# motor_driver.net
KiCad netlist of a schematic drawn in EAGLE
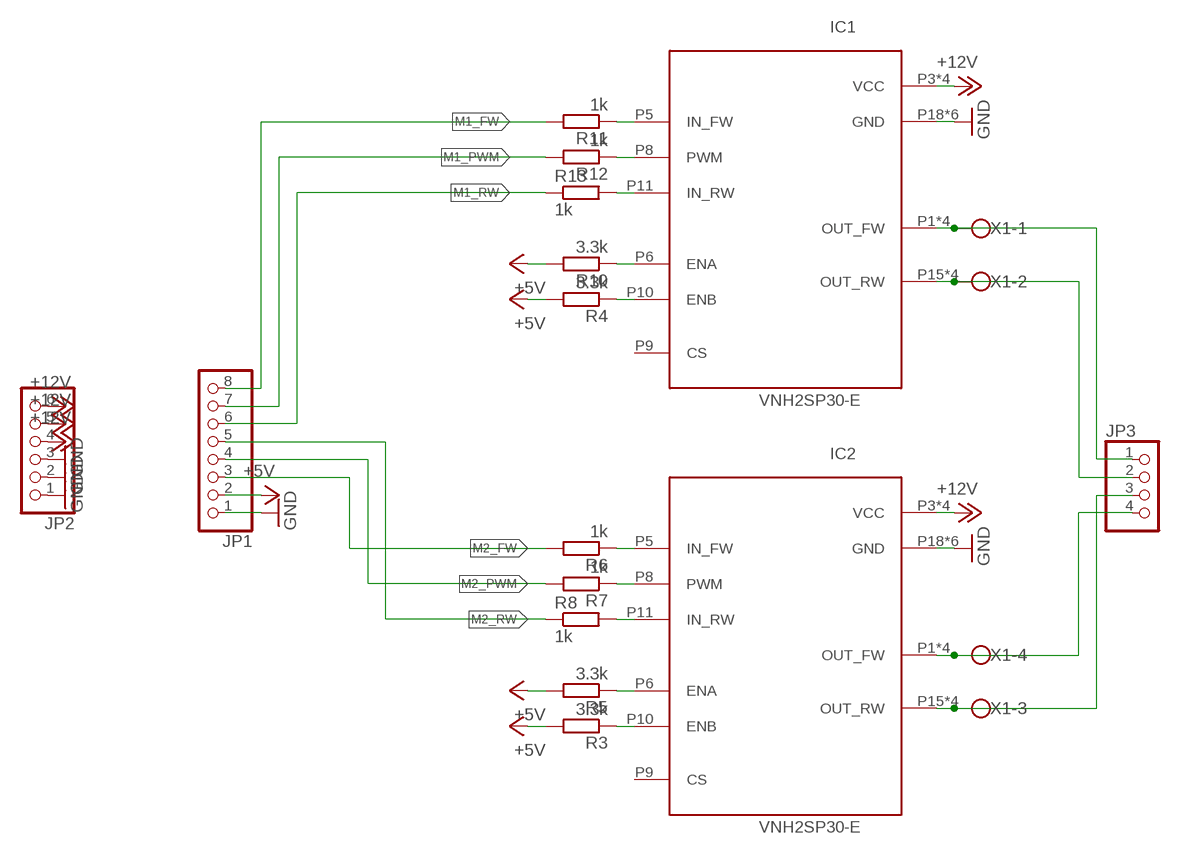
[diagram p0: schematic, sheet 1]

(export (version "E")
  (design (tool "Eeschema 10.0.6"))
  (components
    (comp (ref "IC1")
      (value "VNH2SP30-E")
      (footprint "eagle-import:MP-SO-30")
      (libsource (lib "eagle-import") (part "VNH2SP30-E"))
    )
    (comp (ref "IC2")
      (value "VNH2SP30-E")
      (footprint "eagle-import:MP-SO-30")
      (libsource (lib "eagle-import") (part "VNH2SP30-E"))
    )
    (comp (ref "JP1")
      (value "PINHD-1X08_2.54-S")
      (footprint "eagle-import:1X08-S")
      (libsource (lib "eagle-import") (part "PINHD-1X08_2.54-S"))
    )
    (comp (ref "JP2")
      (value "PINHD-1X06_2.54-S")
      (footprint "eagle-import:1X06-S")
      (libsource (lib "eagle-import") (part "PINHD-1X06_2.54-S"))
    )
    (comp (ref "JP3")
      (value "PINHD-1X04_2.54-S")
      (footprint "eagle-import:1X04-S")
      (libsource (lib "eagle-import") (part "PINHD-1X04_2.54-S"))
    )
    (comp (ref "R3")
      (value "3.3k")
      (footprint "eagle-import:R0805")
      (libsource (lib "eagle-import") (part "R-EU_R0805"))
    )
    (comp (ref "R4")
      (value "3.3k")
      (footprint "eagle-import:R0805")
      (libsource (lib "eagle-import") (part "R-EU_R0805"))
    )
    (comp (ref "R5")
      (value "3.3k")
      (footprint "eagle-import:R0805")
      (libsource (lib "eagle-import") (part "R-EU_R0805"))
    )
    (comp (ref "R6")
      (value "1k")
      (footprint "eagle-import:R0805")
      (libsource (lib "eagle-import") (part "R-EU_R0805"))
    )
    (comp (ref "R7")
      (value "1k")
      (footprint "eagle-import:R0805")
      (libsource (lib "eagle-import") (part "R-EU_R0805"))
    )
    (comp (ref "R8")
      (value "1k")
      (footprint "eagle-import:R0805")
      (libsource (lib "eagle-import") (part "R-EU_R0805"))
    )
    (comp (ref "R10")
      (value "3.3k")
      (footprint "eagle-import:R0805")
      (libsource (lib "eagle-import") (part "R-EU_R0805"))
    )
    (comp (ref "R11")
      (value "1k")
      (footprint "eagle-import:R0805")
      (libsource (lib "eagle-import") (part "R-EU_R0805"))
    )
    (comp (ref "R12")
      (value "1k")
      (footprint "eagle-import:R0805")
      (libsource (lib "eagle-import") (part "R-EU_R0805"))
    )
    (comp (ref "R13")
      (value "1k")
      (footprint "eagle-import:R0805")
      (libsource (lib "eagle-import") (part "R-EU_R0805"))
    )
    (comp (ref "X1")
      (value "KLEMME_4-PIN")
      (footprint "eagle-import:KLEMME_4-PIN")
      (libsource (lib "eagle-import") (part "KLEMME_4-PIN"))
    )
  )
  (nets
    (net (code "1") (name "+5V") (class "Default")
      (node (ref "JP1") (pin "2") (pinfunction "2_2") (pintype "passive"))
      (node (ref "R10") (pin "2") (pinfunction "2_2") (pintype "passive"))
      (node (ref "R3") (pin "2") (pinfunction "2_2") (pintype "passive"))
      (node (ref "R4") (pin "2") (pinfunction "2_2") (pintype "passive"))
      (node (ref "R5") (pin "2") (pinfunction "2_2") (pintype "passive"))
    )
    (net (code "2") (name "+12V") (class "Default")
      (node (ref "IC1") (pin "P13") (pinfunction "VCC_P13") (pintype "power_in"))
      (node (ref "IC1") (pin "P23") (pinfunction "VCC_P23") (pintype "power_in"))
      (node (ref "IC1") (pin "P3") (pinfunction "VCC_P3") (pintype "power_in"))
      (node (ref "IC1") (pin "S1") (pinfunction "VCC_S1") (pintype "power_in"))
      (node (ref "IC2") (pin "P13") (pinfunction "VCC_P13") (pintype "power_in"))
      (node (ref "IC2") (pin "P23") (pinfunction "VCC_P23") (pintype "power_in"))
      (node (ref "IC2") (pin "P3") (pinfunction "VCC_P3") (pintype "power_in"))
      (node (ref "IC2") (pin "S1") (pinfunction "VCC_S1") (pintype "power_in"))
      (node (ref "JP2") (pin "4") (pinfunction "4_4") (pintype "passive"))
      (node (ref "JP2") (pin "5") (pinfunction "5_5") (pintype "passive"))
      (node (ref "JP2") (pin "6") (pinfunction "6_6") (pintype "passive"))
    )
    (net (code "3") (name "GND") (class "Default")
      (node (ref "IC1") (pin "P18") (pinfunction "GND_P18") (pintype "power_in"))
      (node (ref "IC1") (pin "P19") (pinfunction "GND_P19") (pintype "power_in"))
      (node (ref "IC1") (pin "P20") (pinfunction "GND_P20") (pintype "power_in"))
      (node (ref "IC1") (pin "P26") (pinfunction "GND_P26") (pintype "power_in"))
      (node (ref "IC1") (pin "P27") (pinfunction "GND_P27") (pintype "power_in"))
      (node (ref "IC1") (pin "P28") (pinfunction "GND_P28") (pintype "power_in"))
      (node (ref "IC2") (pin "P18") (pinfunction "GND_P18") (pintype "power_in"))
      (node (ref "IC2") (pin "P19") (pinfunction "GND_P19") (pintype "power_in"))
      (node (ref "IC2") (pin "P20") (pinfunction "GND_P20") (pintype "power_in"))
      (node (ref "IC2") (pin "P26") (pinfunction "GND_P26") (pintype "power_in"))
      (node (ref "IC2") (pin "P27") (pinfunction "GND_P27") (pintype "power_in"))
      (node (ref "IC2") (pin "P28") (pinfunction "GND_P28") (pintype "power_in"))
      (node (ref "JP1") (pin "1") (pinfunction "1_1") (pintype "passive"))
      (node (ref "JP2") (pin "1") (pinfunction "1_1") (pintype "passive"))
      (node (ref "JP2") (pin "2") (pinfunction "2_2") (pintype "passive"))
      (node (ref "JP2") (pin "3") (pinfunction "3_3") (pintype "passive"))
    )
    (net (code "4") (name "M1_FW") (class "Default")
      (node (ref "JP1") (pin "8") (pinfunction "8_8") (pintype "passive"))
      (node (ref "R11") (pin "2") (pinfunction "2_2") (pintype "passive"))
    )
    (net (code "5") (name "M1_PWM") (class "Default")
      (node (ref "JP1") (pin "7") (pinfunction "7_7") (pintype "passive"))
      (node (ref "R12") (pin "2") (pinfunction "2_2") (pintype "passive"))
    )
    (net (code "6") (name "M1_RW") (class "Default")
      (node (ref "JP1") (pin "6") (pinfunction "6_6") (pintype "passive"))
      (node (ref "R13") (pin "1") (pinfunction "1_1") (pintype "passive"))
    )
    (net (code "7") (name "M2_FW") (class "Default")
      (node (ref "JP1") (pin "3") (pinfunction "3_3") (pintype "passive"))
      (node (ref "R6") (pin "2") (pinfunction "2_2") (pintype "passive"))
    )
    (net (code "8") (name "M2_PWM") (class "Default")
      (node (ref "JP1") (pin "4") (pinfunction "4_4") (pintype "passive"))
      (node (ref "R7") (pin "2") (pinfunction "2_2") (pintype "passive"))
    )
    (net (code "9") (name "M2_RW") (class "Default")
      (node (ref "JP1") (pin "5") (pinfunction "5_5") (pintype "passive"))
      (node (ref "R8") (pin "1") (pinfunction "1_1") (pintype "passive"))
    )
    (net (code "10") (name "Net-(IC1-ENA)") (class "Default")
      (node (ref "IC1") (pin "P6") (pinfunction "ENA_P6") (pintype "input"))
      (node (ref "R10") (pin "1") (pinfunction "1_1") (pintype "passive"))
    )
    (net (code "11") (name "Net-(IC1-ENB)") (class "Default")
      (node (ref "IC1") (pin "P10") (pinfunction "ENB_P10") (pintype "input"))
      (node (ref "R4") (pin "1") (pinfunction "1_1") (pintype "passive"))
    )
    (net (code "12") (name "Net-(IC1-IN_FW)") (class "Default")
      (node (ref "IC1") (pin "P5") (pinfunction "IN_FW_P5") (pintype "input"))
      (node (ref "R11") (pin "1") (pinfunction "1_1") (pintype "passive"))
    )
    (net (code "13") (name "Net-(IC1-IN_RW)") (class "Default")
      (node (ref "IC1") (pin "P11") (pinfunction "IN_RW_P11") (pintype "input"))
      (node (ref "R13") (pin "2") (pinfunction "2_2") (pintype "passive"))
    )
    (net (code "14") (name "Net-(IC1-PWM)") (class "Default")
      (node (ref "IC1") (pin "P8") (pinfunction "PWM_P8") (pintype "input"))
      (node (ref "R12") (pin "1") (pinfunction "1_1") (pintype "passive"))
    )
    (net (code "15") (name "Net-(IC2-ENA)") (class "Default")
      (node (ref "IC2") (pin "P6") (pinfunction "ENA_P6") (pintype "input"))
      (node (ref "R5") (pin "1") (pinfunction "1_1") (pintype "passive"))
    )
    (net (code "16") (name "Net-(IC2-ENB)") (class "Default")
      (node (ref "IC2") (pin "P10") (pinfunction "ENB_P10") (pintype "input"))
      (node (ref "R3") (pin "1") (pinfunction "1_1") (pintype "passive"))
    )
    (net (code "17") (name "Net-(IC2-IN_FW)") (class "Default")
      (node (ref "IC2") (pin "P5") (pinfunction "IN_FW_P5") (pintype "input"))
      (node (ref "R6") (pin "1") (pinfunction "1_1") (pintype "passive"))
    )
    (net (code "18") (name "Net-(IC2-IN_RW)") (class "Default")
      (node (ref "IC2") (pin "P11") (pinfunction "IN_RW_P11") (pintype "input"))
      (node (ref "R8") (pin "2") (pinfunction "2_2") (pintype "passive"))
    )
    (net (code "19") (name "Net-(IC2-PWM)") (class "Default")
      (node (ref "IC2") (pin "P8") (pinfunction "PWM_P8") (pintype "input"))
      (node (ref "R7") (pin "1") (pinfunction "1_1") (pintype "passive"))
    )
    (net (code "20") (name "Net-(X1A-KL)") (class "Default")
      (node (ref "IC1") (pin "P1") (pinfunction "OUT_FW_P1") (pintype "output"))
      (node (ref "IC1") (pin "P25") (pinfunction "OUT_FW_P25") (pintype "output"))
      (node (ref "IC1") (pin "P30") (pinfunction "OUT_FW_P30") (pintype "output"))
      (node (ref "IC1") (pin "S2") (pinfunction "OUT_FW_S2") (pintype "output"))
      (node (ref "JP3") (pin "1") (pinfunction "1_1") (pintype "passive"))
      (node (ref "X1") (pin "1") (pinfunction "KL_1") (pintype "passive"))
    )
    (net (code "21") (name "Net-(X1B-KL)") (class "Default")
      (node (ref "IC1") (pin "P15") (pinfunction "OUT_RW_P15") (pintype "output"))
      (node (ref "IC1") (pin "P16") (pinfunction "OUT_RW_P16") (pintype "output"))
      (node (ref "IC1") (pin "P21") (pinfunction "OUT_RW_P21") (pintype "output"))
      (node (ref "IC1") (pin "S3") (pinfunction "OUT_RW_S3") (pintype "output"))
      (node (ref "JP3") (pin "2") (pinfunction "2_2") (pintype "passive"))
      (node (ref "X1") (pin "2") (pinfunction "KL_2") (pintype "passive"))
    )
    (net (code "22") (name "Net-(X1C-KL)") (class "Default")
      (node (ref "IC2") (pin "P15") (pinfunction "OUT_RW_P15") (pintype "output"))
      (node (ref "IC2") (pin "P16") (pinfunction "OUT_RW_P16") (pintype "output"))
      (node (ref "IC2") (pin "P21") (pinfunction "OUT_RW_P21") (pintype "output"))
      (node (ref "IC2") (pin "S3") (pinfunction "OUT_RW_S3") (pintype "output"))
      (node (ref "JP3") (pin "3") (pinfunction "3_3") (pintype "passive"))
      (node (ref "X1") (pin "3") (pinfunction "KL_3") (pintype "passive"))
    )
    (net (code "23") (name "Net-(X1D-KL)") (class "Default")
      (node (ref "IC2") (pin "P1") (pinfunction "OUT_FW_P1") (pintype "output"))
      (node (ref "IC2") (pin "P25") (pinfunction "OUT_FW_P25") (pintype "output"))
      (node (ref "IC2") (pin "P30") (pinfunction "OUT_FW_P30") (pintype "output"))
      (node (ref "IC2") (pin "S2") (pinfunction "OUT_FW_S2") (pintype "output"))
      (node (ref "JP3") (pin "4") (pinfunction "4_4") (pintype "passive"))
      (node (ref "X1") (pin "4") (pinfunction "KL_4") (pintype "passive"))
    )
    (net (code "24") (name "unconnected-(IC1-CS-PadP9)") (class "Default")
      (node (ref "IC1") (pin "P9") (pinfunction "CS_P9") (pintype "input"))
    )
    (net (code "25") (name "unconnected-(IC2-CS-PadP9)") (class "Default")
      (node (ref "IC2") (pin "P9") (pinfunction "CS_P9") (pintype "input"))
    )
  )
)
